# ifog-pcb-analogModule.net
KiCad netlist of a schematic drawn in Altium Designer
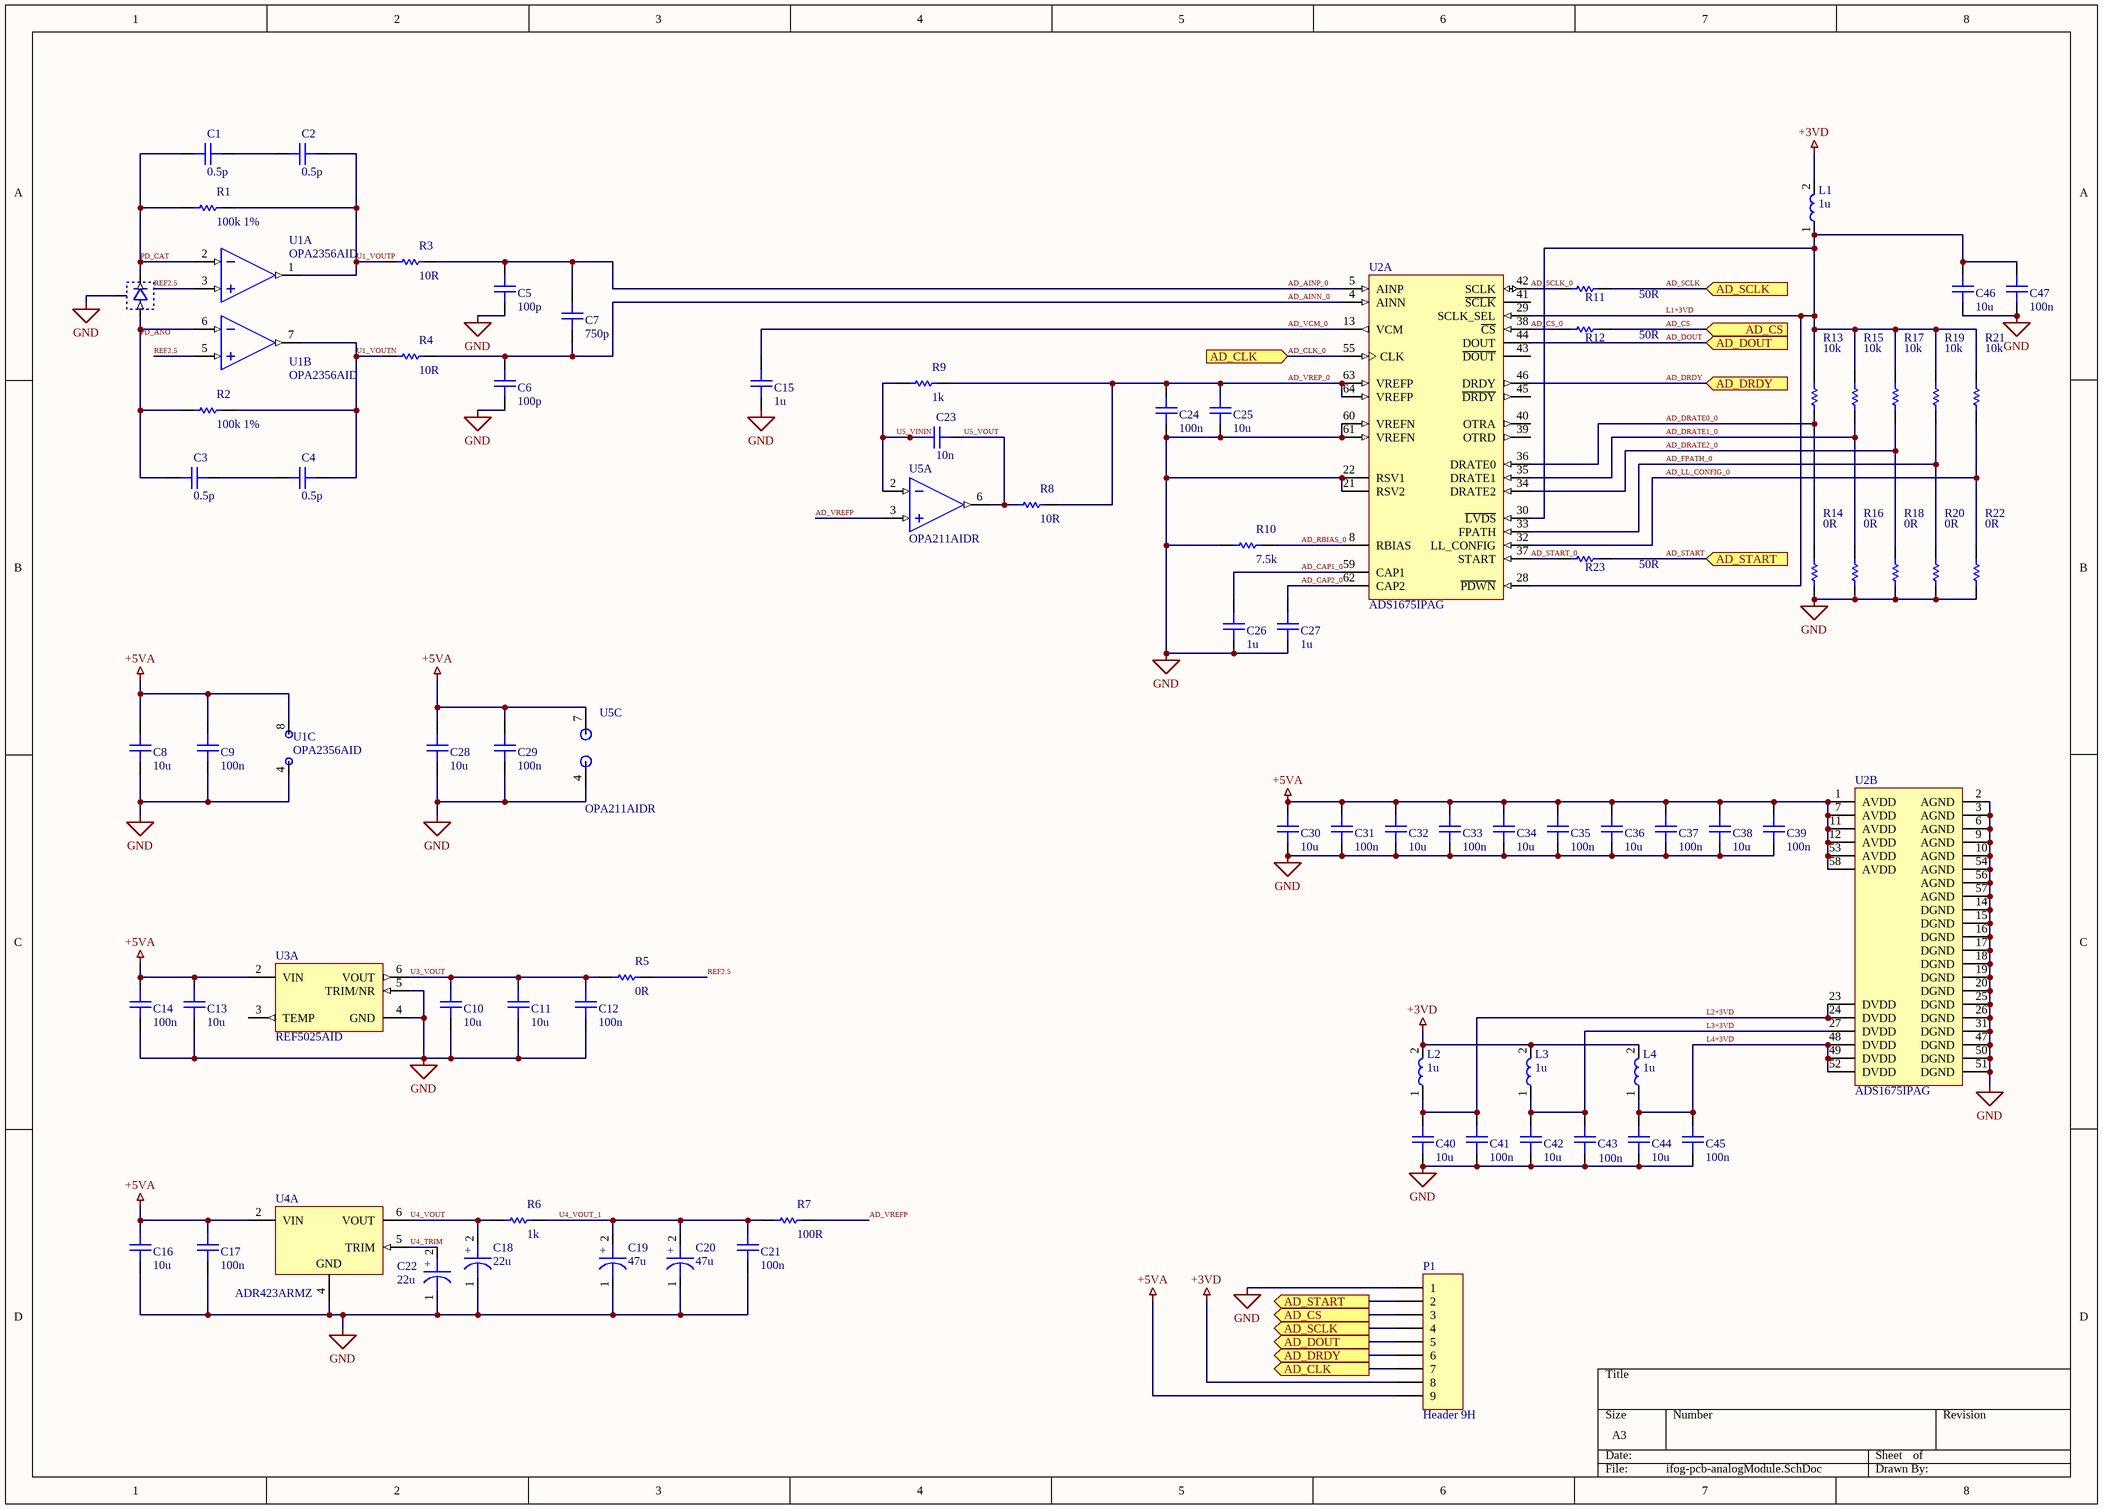
[diagram p0: ifog-pcb-analogModule.SchDoc]

(export (version "E")
  (design (tool "Eeschema 10.0.6"))
  (components
    (comp (ref "C1")
      (value "0.5p")
      (footprint "CAPACITOR_0603")
      (fields (field (name "PART NUMBER") "C0603C105K3RACTU") (field (name "MANUFACTURER") "KEMET"))
      (libsource (lib "ifog-pcb") (part "CAPACITOR_0603"))
    )
    (comp (ref "C2")
      (value "0.5p")
      (footprint "CAPACITOR_0603")
      (fields (field (name "PART NUMBER") "C0603C105K3RACTU") (field (name "MANUFACTURER") "KEMET"))
      (libsource (lib "ifog-pcb") (part "CAPACITOR_0603"))
    )
    (comp (ref "C3")
      (value "0.5p")
      (footprint "CAPACITOR_0603")
      (fields (field (name "PART NUMBER") "C0603C105K3RACTU") (field (name "MANUFACTURER") "KEMET"))
      (libsource (lib "ifog-pcb") (part "CAPACITOR_0603"))
    )
    (comp (ref "C4")
      (value "0.5p")
      (footprint "CAPACITOR_0603")
      (fields (field (name "PART NUMBER") "C0603C105K3RACTU") (field (name "MANUFACTURER") "KEMET"))
      (libsource (lib "ifog-pcb") (part "CAPACITOR_0603"))
    )
    (comp (ref "C5")
      (value "100p")
      (footprint "CAPACITOR_0603")
      (fields (field (name "PART NUMBER") "C0603C105K3RACTU") (field (name "MANUFACTURER") "KEMET"))
      (libsource (lib "ifog-pcb") (part "CAPACITOR_0603"))
    )
    (comp (ref "C6")
      (value "100p")
      (footprint "CAPACITOR_0603")
      (fields (field (name "PART NUMBER") "C0603C105K3RACTU") (field (name "MANUFACTURER") "KEMET"))
      (libsource (lib "ifog-pcb") (part "CAPACITOR_0603"))
    )
    (comp (ref "C7")
      (value "750p")
      (footprint "CAPACITOR_0603")
      (fields (field (name "PART NUMBER") "C0603C105K3RACTU") (field (name "MANUFACTURER") "KEMET"))
      (libsource (lib "ifog-pcb") (part "CAPACITOR_0603"))
    )
    (comp (ref "C8")
      (value "10u")
      (footprint "CAPACITOR_0603")
      (fields (field (name "PART NUMBER") "C0603C105K3RACTU") (field (name "MANUFACTURER") "KEMET"))
      (libsource (lib "ifog-pcb") (part "CAPACITOR_0603"))
    )
    (comp (ref "C9")
      (value "100n")
      (footprint "CAPACITOR_0603")
      (fields (field (name "PART NUMBER") "C0603C105K3RACTU") (field (name "MANUFACTURER") "KEMET"))
      (libsource (lib "ifog-pcb") (part "CAPACITOR_0603"))
    )
    (comp (ref "C10")
      (value "10u")
      (footprint "CAPACITOR_0603")
      (fields (field (name "PART NUMBER") "C0603C105K3RACTU") (field (name "MANUFACTURER") "KEMET"))
      (libsource (lib "ifog-pcb") (part "CAPACITOR_0603"))
    )
    (comp (ref "C11")
      (value "10u")
      (footprint "CAPACITOR_0603")
      (fields (field (name "PART NUMBER") "C0603C105K3RACTU") (field (name "MANUFACTURER") "KEMET"))
      (libsource (lib "ifog-pcb") (part "CAPACITOR_0603"))
    )
    (comp (ref "C12")
      (value "100n")
      (footprint "CAPACITOR_0603")
      (fields (field (name "PART NUMBER") "C0603C105K3RACTU") (field (name "MANUFACTURER") "KEMET"))
      (libsource (lib "ifog-pcb") (part "CAPACITOR_0603"))
    )
    (comp (ref "C13")
      (value "10u")
      (footprint "CAPACITOR_0603")
      (fields (field (name "PART NUMBER") "C0603C105K3RACTU") (field (name "MANUFACTURER") "KEMET"))
      (libsource (lib "ifog-pcb") (part "CAPACITOR_0603"))
    )
    (comp (ref "C14")
      (value "100n")
      (footprint "CAPACITOR_0603")
      (fields (field (name "PART NUMBER") "C0603C105K3RACTU") (field (name "MANUFACTURER") "KEMET"))
      (libsource (lib "ifog-pcb") (part "CAPACITOR_0603"))
    )
    (comp (ref "C15")
      (value "1u")
      (footprint "CAPACITOR_0603")
      (fields (field (name "PART NUMBER") "C0603C105K3RACTU") (field (name "MANUFACTURER") "KEMET"))
      (libsource (lib "ifog-pcb") (part "CAPACITOR_0603"))
    )
    (comp (ref "C16")
      (value "10u")
      (footprint "CAPACITOR_0603")
      (fields (field (name "PART NUMBER") "C0603C105K3RACTU") (field (name "MANUFACTURER") "KEMET"))
      (libsource (lib "ifog-pcb") (part "CAPACITOR_0603"))
    )
    (comp (ref "C17")
      (value "100n")
      (footprint "CAPACITOR_0603")
      (fields (field (name "PART NUMBER") "C0603C105K3RACTU") (field (name "MANUFACTURER") "KEMET"))
      (libsource (lib "ifog-pcb") (part "CAPACITOR_0603"))
    )
    (comp (ref "C18")
      (value "22u")
      (footprint "CAPACITOR_TANT_0603")
      (description "CAP TANT 0603")
      (fields (field (name "TOLERANCE") "20%") (field (name "MANUFACTURER") "Kyocera AVX"))
      (libsource (lib "ifog-pcb") (part "CAPACITOR_TANT_0603"))
    )
    (comp (ref "C19")
      (value "47u")
      (footprint "CAPACITOR_TANT_0603")
      (description "CAP TANT 0603")
      (fields (field (name "TOLERANCE") "20%") (field (name "MANUFACTURER") "Kyocera AVX"))
      (libsource (lib "ifog-pcb") (part "CAPACITOR_TANT_0603"))
    )
    (comp (ref "C20")
      (value "47u")
      (footprint "CAPACITOR_TANT_0603")
      (description "CAP TANT 0603")
      (fields (field (name "TOLERANCE") "20%") (field (name "MANUFACTURER") "Kyocera AVX"))
      (libsource (lib "ifog-pcb") (part "CAPACITOR_TANT_0603"))
    )
    (comp (ref "C21")
      (value "100n")
      (footprint "CAPACITOR_0603")
      (fields (field (name "PART NUMBER") "C0603C105K3RACTU") (field (name "MANUFACTURER") "KEMET"))
      (libsource (lib "ifog-pcb") (part "CAPACITOR_0603"))
    )
    (comp (ref "C22")
      (value "22u")
      (footprint "CAPACITOR_TANT_0603")
      (description "CAP TANT 0603")
      (fields (field (name "TOLERANCE") "20%") (field (name "MANUFACTURER") "Kyocera AVX"))
      (libsource (lib "ifog-pcb") (part "CAPACITOR_TANT_0603"))
    )
    (comp (ref "C23")
      (value "10n")
      (footprint "CAPACITOR_0603")
      (fields (field (name "PART NUMBER") "C0603C105K3RACTU") (field (name "MANUFACTURER") "KEMET"))
      (libsource (lib "ifog-pcb") (part "CAPACITOR_0603"))
    )
    (comp (ref "C24")
      (value "100n")
      (footprint "CAPACITOR_0603")
      (fields (field (name "PART NUMBER") "C0603C105K3RACTU") (field (name "MANUFACTURER") "KEMET"))
      (libsource (lib "ifog-pcb") (part "CAPACITOR_0603"))
    )
    (comp (ref "C25")
      (value "10u")
      (footprint "CAPACITOR_0603")
      (fields (field (name "PART NUMBER") "C0603C105K3RACTU") (field (name "MANUFACTURER") "KEMET"))
      (libsource (lib "ifog-pcb") (part "CAPACITOR_0603"))
    )
    (comp (ref "C26")
      (value "1u")
      (footprint "CAPACITOR_0603")
      (fields (field (name "PART NUMBER") "C0603C105K3RACTU") (field (name "MANUFACTURER") "KEMET"))
      (libsource (lib "ifog-pcb") (part "CAPACITOR_0603"))
    )
    (comp (ref "C27")
      (value "1u")
      (footprint "CAPACITOR_0603")
      (fields (field (name "PART NUMBER") "C0603C105K3RACTU") (field (name "MANUFACTURER") "KEMET"))
      (libsource (lib "ifog-pcb") (part "CAPACITOR_0603"))
    )
    (comp (ref "C28")
      (value "10u")
      (footprint "CAPACITOR_0603")
      (fields (field (name "PART NUMBER") "C0603C105K3RACTU") (field (name "MANUFACTURER") "KEMET"))
      (libsource (lib "ifog-pcb") (part "CAPACITOR_0603"))
    )
    (comp (ref "C29")
      (value "100n")
      (footprint "CAPACITOR_0603")
      (fields (field (name "PART NUMBER") "C0603C105K3RACTU") (field (name "MANUFACTURER") "KEMET"))
      (libsource (lib "ifog-pcb") (part "CAPACITOR_0603"))
    )
    (comp (ref "C30")
      (value "10u")
      (footprint "CAPACITOR_0603")
      (fields (field (name "PART NUMBER") "C0603C105K3RACTU") (field (name "MANUFACTURER") "KEMET"))
      (libsource (lib "ifog-pcb") (part "CAPACITOR_0603"))
    )
    (comp (ref "C31")
      (value "100n")
      (footprint "CAPACITOR_0603")
      (fields (field (name "PART NUMBER") "C0603C105K3RACTU") (field (name "MANUFACTURER") "KEMET"))
      (libsource (lib "ifog-pcb") (part "CAPACITOR_0603"))
    )
    (comp (ref "C32")
      (value "10u")
      (footprint "CAPACITOR_0603")
      (fields (field (name "PART NUMBER") "C0603C105K3RACTU") (field (name "MANUFACTURER") "KEMET"))
      (libsource (lib "ifog-pcb") (part "CAPACITOR_0603"))
    )
    (comp (ref "C33")
      (value "100n")
      (footprint "CAPACITOR_0603")
      (fields (field (name "PART NUMBER") "C0603C105K3RACTU") (field (name "MANUFACTURER") "KEMET"))
      (libsource (lib "ifog-pcb") (part "CAPACITOR_0603"))
    )
    (comp (ref "C34")
      (value "10u")
      (footprint "CAPACITOR_0603")
      (fields (field (name "PART NUMBER") "C0603C105K3RACTU") (field (name "MANUFACTURER") "KEMET"))
      (libsource (lib "ifog-pcb") (part "CAPACITOR_0603"))
    )
    (comp (ref "C35")
      (value "100n")
      (footprint "CAPACITOR_0603")
      (fields (field (name "PART NUMBER") "C0603C105K3RACTU") (field (name "MANUFACTURER") "KEMET"))
      (libsource (lib "ifog-pcb") (part "CAPACITOR_0603"))
    )
    (comp (ref "C36")
      (value "10u")
      (footprint "CAPACITOR_0603")
      (fields (field (name "PART NUMBER") "C0603C105K3RACTU") (field (name "MANUFACTURER") "KEMET"))
      (libsource (lib "ifog-pcb") (part "CAPACITOR_0603"))
    )
    (comp (ref "C37")
      (value "100n")
      (footprint "CAPACITOR_0603")
      (fields (field (name "PART NUMBER") "C0603C105K3RACTU") (field (name "MANUFACTURER") "KEMET"))
      (libsource (lib "ifog-pcb") (part "CAPACITOR_0603"))
    )
    (comp (ref "C38")
      (value "10u")
      (footprint "CAPACITOR_0603")
      (fields (field (name "PART NUMBER") "C0603C105K3RACTU") (field (name "MANUFACTURER") "KEMET"))
      (libsource (lib "ifog-pcb") (part "CAPACITOR_0603"))
    )
    (comp (ref "C39")
      (value "100n")
      (footprint "CAPACITOR_0603")
      (fields (field (name "PART NUMBER") "C0603C105K3RACTU") (field (name "MANUFACTURER") "KEMET"))
      (libsource (lib "ifog-pcb") (part "CAPACITOR_0603"))
    )
    (comp (ref "C40")
      (value "10u")
      (footprint "CAPACITOR_0603")
      (fields (field (name "PART NUMBER") "C0603C105K3RACTU") (field (name "MANUFACTURER") "KEMET"))
      (libsource (lib "ifog-pcb") (part "CAPACITOR_0603"))
    )
    (comp (ref "C41")
      (value "100n")
      (footprint "CAPACITOR_0603")
      (fields (field (name "PART NUMBER") "C0603C105K3RACTU") (field (name "MANUFACTURER") "KEMET"))
      (libsource (lib "ifog-pcb") (part "CAPACITOR_0603"))
    )
    (comp (ref "C42")
      (value "10u")
      (footprint "CAPACITOR_0603")
      (fields (field (name "PART NUMBER") "C0603C105K3RACTU") (field (name "MANUFACTURER") "KEMET"))
      (libsource (lib "ifog-pcb") (part "CAPACITOR_0603"))
    )
    (comp (ref "C43")
      (value "100n")
      (footprint "CAPACITOR_0603")
      (fields (field (name "PART NUMBER") "C0603C105K3RACTU") (field (name "MANUFACTURER") "KEMET"))
      (libsource (lib "ifog-pcb") (part "CAPACITOR_0603"))
    )
    (comp (ref "C44")
      (value "10u")
      (footprint "CAPACITOR_0603")
      (fields (field (name "PART NUMBER") "C0603C105K3RACTU") (field (name "MANUFACTURER") "KEMET"))
      (libsource (lib "ifog-pcb") (part "CAPACITOR_0603"))
    )
    (comp (ref "C45")
      (value "100n")
      (footprint "CAPACITOR_0603")
      (fields (field (name "PART NUMBER") "C0603C105K3RACTU") (field (name "MANUFACTURER") "KEMET"))
      (libsource (lib "ifog-pcb") (part "CAPACITOR_0603"))
    )
    (comp (ref "C46")
      (value "10u")
      (footprint "CAPACITOR_0603")
      (fields (field (name "PART NUMBER") "C0603C105K3RACTU") (field (name "MANUFACTURER") "KEMET"))
      (libsource (lib "ifog-pcb") (part "CAPACITOR_0603"))
    )
    (comp (ref "C47")
      (value "100n")
      (footprint "CAPACITOR_0603")
      (fields (field (name "PART NUMBER") "C0603C105K3RACTU") (field (name "MANUFACTURER") "KEMET"))
      (libsource (lib "ifog-pcb") (part "CAPACITOR_0603"))
    )
    (comp (ref "L1")
      (value "1u")
      (footprint "INDUCTOR_0603")
      (description "FIXED IND SMD")
      (fields (field (name "TOLERANCE") "20%") (field (name "MANUFACTURER") "Murata"))
      (libsource (lib "ifog-pcb") (part "INDUCTOR_0603"))
    )
    (comp (ref "L2")
      (value "1u")
      (footprint "INDUCTOR_0603")
      (description "FIXED IND SMD")
      (fields (field (name "TOLERANCE") "20%") (field (name "MANUFACTURER") "Murata"))
      (libsource (lib "ifog-pcb") (part "INDUCTOR_0603"))
    )
    (comp (ref "L3")
      (value "1u")
      (footprint "INDUCTOR_0603")
      (description "FIXED IND SMD")
      (fields (field (name "TOLERANCE") "20%") (field (name "MANUFACTURER") "Murata"))
      (libsource (lib "ifog-pcb") (part "INDUCTOR_0603"))
    )
    (comp (ref "L4")
      (value "1u")
      (footprint "INDUCTOR_0603")
      (description "FIXED IND SMD")
      (fields (field (name "TOLERANCE") "20%") (field (name "MANUFACTURER") "Murata"))
      (libsource (lib "ifog-pcb") (part "INDUCTOR_0603"))
    )
    (comp (ref "P1")
      (value "Header 9H")
      (footprint "HDR1X9H")
      (description "Header, 9-Pin, Right Angle")
      (fields (field (name "PUBLISHER") "Altium Limited"))
      (libsource (lib "Miscellaneous Connectors") (part "Header 9H"))
    )
    (comp (ref "PD1")
      (value "PDS123-CSA-C0102")
      (footprint "Photodetector")
      (description "Photodiode 3 pins")
      (libsource (lib "ifog-pcb") (part "PDS123-CSA-C0102"))
    )
    (comp (ref "R1")
      (value "100k 1%")
      (footprint "RESISTOR_0603")
      (description "Chip Resistor 0603 (1608 Metric), RoHS, Tape and Reel")
      (fields
        (field (name "MANUFACTURER") "Vishay")
        (field (name "MANUFACTURER PART NUMBER") "CRCW060310K0FKEA")
      )
      (libsource (lib "ifog-pcb") (part "RESISTOR_0603"))
    )
    (comp (ref "R2")
      (value "100k 1%")
      (footprint "RESISTOR_0603")
      (description "Chip Resistor 0603 (1608 Metric), RoHS, Tape and Reel")
      (fields
        (field (name "MANUFACTURER") "Vishay")
        (field (name "MANUFACTURER PART NUMBER") "CRCW060310K0FKEA")
      )
      (libsource (lib "ifog-pcb") (part "RESISTOR_0603"))
    )
    (comp (ref "R3")
      (value "10R")
      (footprint "RESISTOR_0603")
      (description "Chip Resistor 0603 (1608 Metric), RoHS, Tape and Reel")
      (fields
        (field (name "MANUFACTURER") "Vishay")
        (field (name "MANUFACTURER PART NUMBER") "CRCW060310K0FKEA")
      )
      (libsource (lib "ifog-pcb") (part "RESISTOR_0603"))
    )
    (comp (ref "R4")
      (value "10R")
      (footprint "RESISTOR_0603")
      (description "Chip Resistor 0603 (1608 Metric), RoHS, Tape and Reel")
      (fields
        (field (name "MANUFACTURER") "Vishay")
        (field (name "MANUFACTURER PART NUMBER") "CRCW060310K0FKEA")
      )
      (libsource (lib "ifog-pcb") (part "RESISTOR_0603"))
    )
    (comp (ref "R5")
      (value "0R")
      (footprint "RESISTOR_0603")
      (description "Chip Resistor 0603 (1608 Metric), RoHS, Tape and Reel")
      (fields
        (field (name "MANUFACTURER") "Vishay")
        (field (name "MANUFACTURER PART NUMBER") "CRCW060310K0FKEA")
      )
      (libsource (lib "ifog-pcb") (part "RESISTOR_0603"))
    )
    (comp (ref "R6")
      (value "1k")
      (footprint "RESISTOR_0603")
      (description "Chip Resistor 0603 (1608 Metric), RoHS, Tape and Reel")
      (fields
        (field (name "MANUFACTURER") "Vishay")
        (field (name "MANUFACTURER PART NUMBER") "CRCW060310K0FKEA")
      )
      (libsource (lib "ifog-pcb") (part "RESISTOR_0603"))
    )
    (comp (ref "R7")
      (value "100R")
      (footprint "RESISTOR_0603")
      (description "Chip Resistor 0603 (1608 Metric), RoHS, Tape and Reel")
      (fields
        (field (name "MANUFACTURER") "Vishay")
        (field (name "MANUFACTURER PART NUMBER") "CRCW060310K0FKEA")
      )
      (libsource (lib "ifog-pcb") (part "RESISTOR_0603"))
    )
    (comp (ref "R8")
      (value "10R")
      (footprint "RESISTOR_0603")
      (description "Chip Resistor 0603 (1608 Metric), RoHS, Tape and Reel")
      (fields
        (field (name "MANUFACTURER") "Vishay")
        (field (name "MANUFACTURER PART NUMBER") "CRCW060310K0FKEA")
      )
      (libsource (lib "ifog-pcb") (part "RESISTOR_0603"))
    )
    (comp (ref "R9")
      (value "1k")
      (footprint "RESISTOR_0603")
      (description "Chip Resistor 0603 (1608 Metric), RoHS, Tape and Reel")
      (fields
        (field (name "MANUFACTURER") "Vishay")
        (field (name "MANUFACTURER PART NUMBER") "CRCW060310K0FKEA")
      )
      (libsource (lib "ifog-pcb") (part "RESISTOR_0603"))
    )
    (comp (ref "R10")
      (value "7.5k")
      (footprint "RESISTOR_0603")
      (description "Chip Resistor 0603 (1608 Metric), RoHS, Tape and Reel")
      (fields
        (field (name "MANUFACTURER") "Vishay")
        (field (name "MANUFACTURER PART NUMBER") "CRCW060310K0FKEA")
      )
      (libsource (lib "ifog-pcb") (part "RESISTOR_0603"))
    )
    (comp (ref "R11")
      (value "50R")
      (footprint "RESISTOR_0603")
      (description "Chip Resistor 0603 (1608 Metric), RoHS, Tape and Reel")
      (fields
        (field (name "MANUFACTURER") "Vishay")
        (field (name "MANUFACTURER PART NUMBER") "CRCW060310K0FKEA")
      )
      (libsource (lib "ifog-pcb") (part "RESISTOR_0603"))
    )
    (comp (ref "R12")
      (value "50R")
      (footprint "RESISTOR_0603")
      (description "Chip Resistor 0603 (1608 Metric), RoHS, Tape and Reel")
      (fields
        (field (name "MANUFACTURER") "Vishay")
        (field (name "MANUFACTURER PART NUMBER") "CRCW060310K0FKEA")
      )
      (libsource (lib "ifog-pcb") (part "RESISTOR_0603"))
    )
    (comp (ref "R13")
      (value "10k")
      (footprint "RESISTOR_0603")
      (description "Chip Resistor 0603 (1608 Metric), RoHS, Tape and Reel")
      (fields
        (field (name "MANUFACTURER") "Vishay")
        (field (name "MANUFACTURER PART NUMBER") "CRCW060310K0FKEA")
      )
      (libsource (lib "ifog-pcb") (part "RESISTOR_0603"))
    )
    (comp (ref "R14")
      (value "0R")
      (footprint "RESISTOR_0603")
      (description "Chip Resistor 0603 (1608 Metric), RoHS, Tape and Reel")
      (fields
        (field (name "MANUFACTURER") "Vishay")
        (field (name "MANUFACTURER PART NUMBER") "CRCW060310K0FKEA")
      )
      (libsource (lib "ifog-pcb") (part "RESISTOR_0603"))
    )
    (comp (ref "R15")
      (value "10k")
      (footprint "RESISTOR_0603")
      (description "Chip Resistor 0603 (1608 Metric), RoHS, Tape and Reel")
      (fields
        (field (name "MANUFACTURER") "Vishay")
        (field (name "MANUFACTURER PART NUMBER") "CRCW060310K0FKEA")
      )
      (libsource (lib "ifog-pcb") (part "RESISTOR_0603"))
    )
    (comp (ref "R16")
      (value "0R")
      (footprint "RESISTOR_0603")
      (description "Chip Resistor 0603 (1608 Metric), RoHS, Tape and Reel")
      (fields
        (field (name "MANUFACTURER") "Vishay")
        (field (name "MANUFACTURER PART NUMBER") "CRCW060310K0FKEA")
      )
      (libsource (lib "ifog-pcb") (part "RESISTOR_0603"))
    )
    (comp (ref "R17")
      (value "10k")
      (footprint "RESISTOR_0603")
      (description "Chip Resistor 0603 (1608 Metric), RoHS, Tape and Reel")
      (fields
        (field (name "MANUFACTURER") "Vishay")
        (field (name "MANUFACTURER PART NUMBER") "CRCW060310K0FKEA")
      )
      (libsource (lib "ifog-pcb") (part "RESISTOR_0603"))
    )
    (comp (ref "R18")
      (value "0R")
      (footprint "RESISTOR_0603")
      (description "Chip Resistor 0603 (1608 Metric), RoHS, Tape and Reel")
      (fields
        (field (name "MANUFACTURER") "Vishay")
        (field (name "MANUFACTURER PART NUMBER") "CRCW060310K0FKEA")
      )
      (libsource (lib "ifog-pcb") (part "RESISTOR_0603"))
    )
    (comp (ref "R19")
      (value "10k")
      (footprint "RESISTOR_0603")
      (description "Chip Resistor 0603 (1608 Metric), RoHS, Tape and Reel")
      (fields
        (field (name "MANUFACTURER") "Vishay")
        (field (name "MANUFACTURER PART NUMBER") "CRCW060310K0FKEA")
      )
      (libsource (lib "ifog-pcb") (part "RESISTOR_0603"))
    )
    (comp (ref "R20")
      (value "0R")
      (footprint "RESISTOR_0603")
      (description "Chip Resistor 0603 (1608 Metric), RoHS, Tape and Reel")
      (fields
        (field (name "MANUFACTURER") "Vishay")
        (field (name "MANUFACTURER PART NUMBER") "CRCW060310K0FKEA")
      )
      (libsource (lib "ifog-pcb") (part "RESISTOR_0603"))
    )
    (comp (ref "R21")
      (value "10k")
      (footprint "RESISTOR_0603")
      (description "Chip Resistor 0603 (1608 Metric), RoHS, Tape and Reel")
      (fields
        (field (name "MANUFACTURER") "Vishay")
        (field (name "MANUFACTURER PART NUMBER") "CRCW060310K0FKEA")
      )
      (libsource (lib "ifog-pcb") (part "RESISTOR_0603"))
    )
    (comp (ref "R22")
      (value "0R")
      (footprint "RESISTOR_0603")
      (description "Chip Resistor 0603 (1608 Metric), RoHS, Tape and Reel")
      (fields
        (field (name "MANUFACTURER") "Vishay")
        (field (name "MANUFACTURER PART NUMBER") "CRCW060310K0FKEA")
      )
      (libsource (lib "ifog-pcb") (part "RESISTOR_0603"))
    )
    (comp (ref "R23")
      (value "50R")
      (footprint "RESISTOR_0603")
      (description "Chip Resistor 0603 (1608 Metric), RoHS, Tape and Reel")
      (fields
        (field (name "MANUFACTURER") "Vishay")
        (field (name "MANUFACTURER PART NUMBER") "CRCW060310K0FKEA")
      )
      (libsource (lib "ifog-pcb") (part "RESISTOR_0603"))
    )
    (comp (ref "U1")
      (value "OPA2356AID")
      (footprint "OPA2356_SOIC8")
      (fields (field (name "MANUFACTURER") "Texas Instruments"))
      (libsource (lib "ifog-pcb") (part "OPA2356AID"))
    )
    (comp (ref "U2")
      (value "ADS1675IPAG")
      (footprint "TI-PAG64_L")
      (description "4 MSPS, 24-Bit ADC, -40 to 85 degC, 64-pin QFP (PAG64), Green (RoHS & no Sb/Br)")
      (fields (field (name "MANUFACTURER") "Texas Instruments"))
      (libsource (lib "ifog-pcb") (part "ADS1675"))
    )
    (comp (ref "U3")
      (value "REF5025AID")
      (footprint "OPA2356_SOIC8")
      (fields (field (name "MANUFACTURER") "Texas Instruments"))
      (libsource (lib "ifog-pcb") (part "REF5025AID"))
    )
    (comp (ref "U4")
      (value "ADR423ARMZ")
      (footprint "ADR423_SOP8")
      (fields (field (name "MANUFACTURER") "Analog Devices"))
      (libsource (lib "ifog-pcb") (part "ADR423ARMZ"))
    )
    (comp (ref "U5")
      (value "OPA211AIDR")
      (footprint "OPA211_SOIC8")
      (fields (field (name "MANUFACTURER") "Texas Instruments"))
      (libsource (lib "ifog-pcb") (part "OPA211AIDR"))
    )
  )
  (nets
    (net (code "1") (name "+3VD") (class "Default")
      (node (ref "L1") (pin "2") (pinfunction "2_2") (pintype "passive"))
      (node (ref "L2") (pin "2") (pinfunction "2_2") (pintype "passive"))
      (node (ref "L3") (pin "2") (pinfunction "2_2") (pintype "passive"))
      (node (ref "L4") (pin "2") (pinfunction "2_2") (pintype "passive"))
      (node (ref "P1") (pin "8") (pinfunction "8_8") (pintype "passive"))
    )
    (net (code "2") (name "+5VA") (class "Default")
      (node (ref "C13") (pin "2") (pinfunction "2_2") (pintype "passive"))
      (node (ref "C14") (pin "2") (pinfunction "2_2") (pintype "passive"))
      (node (ref "C16") (pin "2") (pinfunction "2_2") (pintype "passive"))
      (node (ref "C17") (pin "2") (pinfunction "2_2") (pintype "passive"))
      (node (ref "C28") (pin "2") (pinfunction "2_2") (pintype "passive"))
      (node (ref "C29") (pin "2") (pinfunction "2_2") (pintype "passive"))
      (node (ref "C30") (pin "2") (pinfunction "2_2") (pintype "passive"))
      (node (ref "C31") (pin "2") (pinfunction "2_2") (pintype "passive"))
      (node (ref "C32") (pin "2") (pinfunction "2_2") (pintype "passive"))
      (node (ref "C33") (pin "2") (pinfunction "2_2") (pintype "passive"))
      (node (ref "C34") (pin "2") (pinfunction "2_2") (pintype "passive"))
      (node (ref "C35") (pin "2") (pinfunction "2_2") (pintype "passive"))
      (node (ref "C36") (pin "2") (pinfunction "2_2") (pintype "passive"))
      (node (ref "C37") (pin "2") (pinfunction "2_2") (pintype "passive"))
      (node (ref "C38") (pin "2") (pinfunction "2_2") (pintype "passive"))
      (node (ref "C39") (pin "2") (pinfunction "2_2") (pintype "passive"))
      (node (ref "C8") (pin "2") (pinfunction "2_2") (pintype "passive"))
      (node (ref "C9") (pin "2") (pinfunction "2_2") (pintype "passive"))
      (node (ref "P1") (pin "9") (pinfunction "9_9") (pintype "passive"))
      (node (ref "U1") (pin "8") (pinfunction "V+_8") (pintype "power_in"))
      (node (ref "U2") (pin "1") (pinfunction "AVDD_1") (pintype "power_in"))
      (node (ref "U2") (pin "11") (pinfunction "AVDD_11") (pintype "power_in"))
      (node (ref "U2") (pin "12") (pinfunction "AVDD_12") (pintype "power_in"))
      (node (ref "U2") (pin "53") (pinfunction "AVDD_53") (pintype "power_in"))
      (node (ref "U2") (pin "58") (pinfunction "AVDD_58") (pintype "power_in"))
      (node (ref "U2") (pin "7") (pinfunction "AVDD_7") (pintype "power_in"))
      (node (ref "U3") (pin "2") (pinfunction "VIN_2") (pintype "power_in"))
      (node (ref "U4") (pin "2") (pinfunction "VIN_2") (pintype "power_in"))
      (node (ref "U5") (pin "7") (pinfunction "V+_7") (pintype "power_in"))
    )
    (net (code "3") (name "/AD_AINN_0") (class "Default")
      (node (ref "C6") (pin "2") (pinfunction "2_2") (pintype "passive"))
      (node (ref "C7") (pin "1") (pinfunction "1_1") (pintype "passive"))
      (node (ref "R4") (pin "2") (pinfunction "2_2") (pintype "passive"))
      (node (ref "U2") (pin "4") (pinfunction "AINN_4") (pintype "input"))
    )
    (net (code "4") (name "/AD_AINP_0") (class "Default")
      (node (ref "C5") (pin "2") (pinfunction "2_2") (pintype "passive"))
      (node (ref "C7") (pin "2") (pinfunction "2_2") (pintype "passive"))
      (node (ref "R3") (pin "2") (pinfunction "2_2") (pintype "passive"))
      (node (ref "U2") (pin "5") (pinfunction "AINP_5") (pintype "input"))
    )
    (net (code "5") (name "/AD_CAP1_0") (class "Default")
      (node (ref "C26") (pin "2") (pinfunction "2_2") (pintype "passive"))
      (node (ref "U2") (pin "59") (pinfunction "CAP1_59") (pintype "passive"))
    )
    (net (code "6") (name "/AD_CAP2_0") (class "Default")
      (node (ref "C27") (pin "2") (pinfunction "2_2") (pintype "passive"))
      (node (ref "U2") (pin "62") (pinfunction "CAP2_62") (pintype "passive"))
    )
    (net (code "7") (name "/AD_CLK_0") (class "Default")
      (node (ref "P1") (pin "7") (pinfunction "7_7") (pintype "passive"))
      (node (ref "U2") (pin "55") (pinfunction "CLK_55") (pintype "input"))
    )
    (net (code "8") (name "/AD_CS") (class "Default")
      (node (ref "P1") (pin "3") (pinfunction "3_3") (pintype "passive"))
      (node (ref "R12") (pin "2") (pinfunction "2_2") (pintype "passive"))
    )
    (net (code "9") (name "/AD_CS_0") (class "Default")
      (node (ref "R12") (pin "1") (pinfunction "1_1") (pintype "passive"))
      (node (ref "U2") (pin "38") (pinfunction "~{CS}_38") (pintype "input"))
    )
    (net (code "10") (name "/AD_DOUT") (class "Default")
      (node (ref "P1") (pin "5") (pinfunction "5_5") (pintype "passive"))
      (node (ref "U2") (pin "44") (pinfunction "DOUT_44") (pintype "tri_state"))
    )
    (net (code "11") (name "/AD_DRATE0_0") (class "Default")
      (node (ref "R13") (pin "1") (pinfunction "1_1") (pintype "passive"))
      (node (ref "R14") (pin "2") (pinfunction "2_2") (pintype "passive"))
      (node (ref "U2") (pin "36") (pinfunction "DRATE0_36") (pintype "input"))
    )
    (net (code "12") (name "/AD_DRATE1_0") (class "Default")
      (node (ref "R15") (pin "1") (pinfunction "1_1") (pintype "passive"))
      (node (ref "R16") (pin "2") (pinfunction "2_2") (pintype "passive"))
      (node (ref "U2") (pin "35") (pinfunction "DRATE1_35") (pintype "input"))
    )
    (net (code "13") (name "/AD_DRATE2_0") (class "Default")
      (node (ref "R17") (pin "1") (pinfunction "1_1") (pintype "passive"))
      (node (ref "R18") (pin "2") (pinfunction "2_2") (pintype "passive"))
      (node (ref "U2") (pin "34") (pinfunction "DRATE2_34") (pintype "input"))
    )
    (net (code "14") (name "/AD_DRDY") (class "Default")
      (node (ref "P1") (pin "6") (pinfunction "6_6") (pintype "passive"))
      (node (ref "U2") (pin "46") (pinfunction "DRDY_46") (pintype "output"))
    )
    (net (code "15") (name "/AD_FPATH_0") (class "Default")
      (node (ref "R19") (pin "1") (pinfunction "1_1") (pintype "passive"))
      (node (ref "R20") (pin "2") (pinfunction "2_2") (pintype "passive"))
      (node (ref "U2") (pin "33") (pinfunction "FPATH_33") (pintype "input"))
    )
    (net (code "16") (name "/AD_LL_CONFIG_0") (class "Default")
      (node (ref "R21") (pin "1") (pinfunction "1_1") (pintype "passive"))
      (node (ref "R22") (pin "2") (pinfunction "2_2") (pintype "passive"))
      (node (ref "U2") (pin "32") (pinfunction "LL_CONFIG_32") (pintype "input"))
    )
    (net (code "17") (name "/AD_RBIAS_0") (class "Default")
      (node (ref "R10") (pin "2") (pinfunction "2_2") (pintype "passive"))
      (node (ref "U2") (pin "8") (pinfunction "RBIAS_8") (pintype "passive"))
    )
    (net (code "18") (name "/AD_SCLK") (class "Default")
      (node (ref "P1") (pin "4") (pinfunction "4_4") (pintype "passive"))
      (node (ref "R11") (pin "2") (pinfunction "2_2") (pintype "passive"))
    )
    (net (code "19") (name "/AD_SCLK_0") (class "Default")
      (node (ref "R11") (pin "1") (pinfunction "1_1") (pintype "passive"))
      (node (ref "U2") (pin "42") (pinfunction "SCLK_42") (pintype "bidirectional"))
    )
    (net (code "20") (name "/AD_START") (class "Default")
      (node (ref "P1") (pin "2") (pinfunction "2_2") (pintype "passive"))
      (node (ref "R23") (pin "2") (pinfunction "2_2") (pintype "passive"))
    )
    (net (code "21") (name "/AD_START_0") (class "Default")
      (node (ref "R23") (pin "1") (pinfunction "1_1") (pintype "passive"))
      (node (ref "U2") (pin "37") (pinfunction "START_37") (pintype "input"))
    )
    (net (code "22") (name "/AD_VCM_0") (class "Default")
      (node (ref "C15") (pin "2") (pinfunction "2_2") (pintype "passive"))
      (node (ref "U2") (pin "13") (pinfunction "VCM_13") (pintype "output"))
    )
    (net (code "23") (name "/AD_VREFP") (class "Default")
      (node (ref "R7") (pin "2") (pinfunction "2_2") (pintype "passive"))
      (node (ref "U5") (pin "3") (pinfunction "IN+_3") (pintype "input"))
    )
    (net (code "24") (name "/AD_VREP_0") (class "Default")
      (node (ref "C24") (pin "2") (pinfunction "2_2") (pintype "passive"))
      (node (ref "C25") (pin "2") (pinfunction "2_2") (pintype "passive"))
      (node (ref "R8") (pin "2") (pinfunction "2_2") (pintype "passive"))
      (node (ref "R9") (pin "2") (pinfunction "2_2") (pintype "passive"))
      (node (ref "U2") (pin "63") (pinfunction "VREFP_63") (pintype "input"))
      (node (ref "U2") (pin "64") (pinfunction "VREFP_64") (pintype "input"))
    )
    (net (code "25") (name "/L1+3VD") (class "Default")
      (node (ref "C46") (pin "2") (pinfunction "2_2") (pintype "passive"))
      (node (ref "C47") (pin "2") (pinfunction "2_2") (pintype "passive"))
      (node (ref "L1") (pin "1") (pinfunction "1_1") (pintype "passive"))
      (node (ref "R13") (pin "2") (pinfunction "2_2") (pintype "passive"))
      (node (ref "R15") (pin "2") (pinfunction "2_2") (pintype "passive"))
      (node (ref "R17") (pin "2") (pinfunction "2_2") (pintype "passive"))
      (node (ref "R19") (pin "2") (pinfunction "2_2") (pintype "passive"))
      (node (ref "R21") (pin "2") (pinfunction "2_2") (pintype "passive"))
      (node (ref "U2") (pin "28") (pinfunction "~{PDWN}_28") (pintype "input"))
      (node (ref "U2") (pin "29") (pinfunction "SCLK_SEL_29") (pintype "input"))
      (node (ref "U2") (pin "30") (pinfunction "~{LVDS}_30") (pintype "input"))
    )
    (net (code "26") (name "/L2+3VD") (class "Default")
      (node (ref "C40") (pin "2") (pinfunction "2_2") (pintype "passive"))
      (node (ref "C41") (pin "2") (pinfunction "2_2") (pintype "passive"))
      (node (ref "L2") (pin "1") (pinfunction "1_1") (pintype "passive"))
      (node (ref "U2") (pin "23") (pinfunction "DVDD_23") (pintype "power_in"))
      (node (ref "U2") (pin "24") (pinfunction "DVDD_24") (pintype "power_in"))
    )
    (net (code "27") (name "/L3+3VD") (class "Default")
      (node (ref "C42") (pin "2") (pinfunction "2_2") (pintype "passive"))
      (node (ref "C43") (pin "2") (pinfunction "2_2") (pintype "passive"))
      (node (ref "L3") (pin "1") (pinfunction "1_1") (pintype "passive"))
      (node (ref "U2") (pin "27") (pinfunction "DVDD_27") (pintype "power_in"))
    )
    (net (code "28") (name "/L4+3VD") (class "Default")
      (node (ref "C44") (pin "2") (pinfunction "2_2") (pintype "passive"))
      (node (ref "C45") (pin "2") (pinfunction "2_2") (pintype "passive"))
      (node (ref "L4") (pin "1") (pinfunction "1_1") (pintype "passive"))
      (node (ref "U2") (pin "48") (pinfunction "DVDD_48") (pintype "power_in"))
      (node (ref "U2") (pin "49") (pinfunction "DVDD_49") (pintype "power_in"))
      (node (ref "U2") (pin "52") (pinfunction "DVDD_52") (pintype "power_in"))
    )
    (net (code "29") (name "/PD_ANO") (class "Default")
      (node (ref "C3") (pin "2") (pinfunction "2_2") (pintype "passive"))
      (node (ref "PD1") (pin "P") (pinfunction "P_P") (pintype "input"))
      (node (ref "R2") (pin "1") (pinfunction "1_1") (pintype "passive"))
      (node (ref "U1") (pin "6") (pinfunction "IN_B-_6") (pintype "input"))
    )
    (net (code "30") (name "/PD_CAT") (class "Default")
      (node (ref "C1") (pin "2") (pinfunction "2_2") (pintype "passive"))
      (node (ref "PD1") (pin "N") (pinfunction "N_N") (pintype "output"))
      (node (ref "R1") (pin "1") (pinfunction "1_1") (pintype "passive"))
      (node (ref "U1") (pin "2") (pinfunction "IN_A-_2") (pintype "input"))
    )
    (net (code "31") (name "/REF2.5") (class "Default")
      (node (ref "R5") (pin "2") (pinfunction "2_2") (pintype "passive"))
      (node (ref "U1") (pin "3") (pinfunction "IN_A+_3") (pintype "input"))
      (node (ref "U1") (pin "5") (pinfunction "IN_B+_5") (pintype "input"))
    )
    (net (code "32") (name "/U1_VOUTN") (class "Default")
      (node (ref "C4") (pin "1") (pinfunction "1_1") (pintype "passive"))
      (node (ref "R2") (pin "2") (pinfunction "2_2") (pintype "passive"))
      (node (ref "R4") (pin "1") (pinfunction "1_1") (pintype "passive"))
      (node (ref "U1") (pin "7") (pinfunction "OUT_B_7") (pintype "output"))
    )
    (net (code "33") (name "/U1_VOUTP") (class "Default")
      (node (ref "C2") (pin "1") (pinfunction "1_1") (pintype "passive"))
      (node (ref "R1") (pin "2") (pinfunction "2_2") (pintype "passive"))
      (node (ref "R3") (pin "1") (pinfunction "1_1") (pintype "passive"))
      (node (ref "U1") (pin "1") (pinfunction "OUT_A_1") (pintype "output"))
    )
    (net (code "34") (name "/U3_VOUT") (class "Default")
      (node (ref "C10") (pin "2") (pinfunction "2_2") (pintype "passive"))
      (node (ref "C11") (pin "2") (pinfunction "2_2") (pintype "passive"))
      (node (ref "C12") (pin "2") (pinfunction "2_2") (pintype "passive"))
      (node (ref "R5") (pin "1") (pinfunction "1_1") (pintype "passive"))
      (node (ref "U3") (pin "6") (pinfunction "VOUT_6") (pintype "output"))
    )
    (net (code "35") (name "/U4_TRIM") (class "Default")
      (node (ref "C22") (pin "2") (pinfunction "A_2") (pintype "passive"))
      (node (ref "U4") (pin "5") (pinfunction "TRIM_5") (pintype "input"))
    )
    (net (code "36") (name "/U4_VOUT") (class "Default")
      (node (ref "C18") (pin "2") (pinfunction "A_2") (pintype "passive"))
      (node (ref "R6") (pin "1") (pinfunction "1_1") (pintype "passive"))
      (node (ref "U4") (pin "6") (pinfunction "VOUT_6") (pintype "power_in"))
    )
    (net (code "37") (name "/U4_VOUT_1") (class "Default")
      (node (ref "C19") (pin "2") (pinfunction "A_2") (pintype "passive"))
      (node (ref "C20") (pin "2") (pinfunction "A_2") (pintype "passive"))
      (node (ref "C21") (pin "2") (pinfunction "2_2") (pintype "passive"))
      (node (ref "R6") (pin "2") (pinfunction "2_2") (pintype "passive"))
      (node (ref "R7") (pin "1") (pinfunction "1_1") (pintype "passive"))
    )
    (net (code "38") (name "/U5_VININ") (class "Default")
      (node (ref "C23") (pin "2") (pinfunction "2_2") (pintype "passive"))
      (node (ref "R9") (pin "1") (pinfunction "1_1") (pintype "passive"))
      (node (ref "U5") (pin "2") (pinfunction "IN-_2") (pintype "input"))
    )
    (net (code "39") (name "/U5_VOUT") (class "Default")
      (node (ref "C23") (pin "1") (pinfunction "1_1") (pintype "passive"))
      (node (ref "R8") (pin "1") (pinfunction "1_1") (pintype "passive"))
      (node (ref "U5") (pin "6") (pinfunction "OUT_6") (pintype "output"))
    )
    (net (code "40") (name "GND") (class "Default")
      (node (ref "C10") (pin "1") (pinfunction "1_1") (pintype "passive"))
      (node (ref "C11") (pin "1") (pinfunction "1_1") (pintype "passive"))
      (node (ref "C12") (pin "1") (pinfunction "1_1") (pintype "passive"))
      (node (ref "C13") (pin "1") (pinfunction "1_1") (pintype "passive"))
      (node (ref "C14") (pin "1") (pinfunction "1_1") (pintype "passive"))
      (node (ref "C15") (pin "1") (pinfunction "1_1") (pintype "passive"))
      (node (ref "C16") (pin "1") (pinfunction "1_1") (pintype "passive"))
      (node (ref "C17") (pin "1") (pinfunction "1_1") (pintype "passive"))
      (node (ref "C18") (pin "1") (pinfunction "C_1") (pintype "passive"))
      (node (ref "C19") (pin "1") (pinfunction "C_1") (pintype "passive"))
      (node (ref "C20") (pin "1") (pinfunction "C_1") (pintype "passive"))
      (node (ref "C21") (pin "1") (pinfunction "1_1") (pintype "passive"))
      (node (ref "C22") (pin "1") (pinfunction "C_1") (pintype "passive"))
      (node (ref "C24") (pin "1") (pinfunction "1_1") (pintype "passive"))
      (node (ref "C25") (pin "1") (pinfunction "1_1") (pintype "passive"))
      (node (ref "C26") (pin "1") (pinfunction "1_1") (pintype "passive"))
      (node (ref "C27") (pin "1") (pinfunction "1_1") (pintype "passive"))
      (node (ref "C28") (pin "1") (pinfunction "1_1") (pintype "passive"))
      (node (ref "C29") (pin "1") (pinfunction "1_1") (pintype "passive"))
      (node (ref "C30") (pin "1") (pinfunction "1_1") (pintype "passive"))
      (node (ref "C31") (pin "1") (pinfunction "1_1") (pintype "passive"))
      (node (ref "C32") (pin "1") (pinfunction "1_1") (pintype "passive"))
      (node (ref "C33") (pin "1") (pinfunction "1_1") (pintype "passive"))
      (node (ref "C34") (pin "1") (pinfunction "1_1") (pintype "passive"))
      (node (ref "C35") (pin "1") (pinfunction "1_1") (pintype "passive"))
      (node (ref "C36") (pin "1") (pinfunction "1_1") (pintype "passive"))
      (node (ref "C37") (pin "1") (pinfunction "1_1") (pintype "passive"))
      (node (ref "C38") (pin "1") (pinfunction "1_1") (pintype "passive"))
      (node (ref "C39") (pin "1") (pinfunction "1_1") (pintype "passive"))
      (node (ref "C40") (pin "1") (pinfunction "1_1") (pintype "passive"))
      (node (ref "C41") (pin "1") (pinfunction "1_1") (pintype "passive"))
      (node (ref "C42") (pin "1") (pinfunction "1_1") (pintype "passive"))
      (node (ref "C43") (pin "1") (pinfunction "1_1") (pintype "passive"))
      (node (ref "C44") (pin "1") (pinfunction "1_1") (pintype "passive"))
      (node (ref "C45") (pin "1") (pinfunction "1_1") (pintype "passive"))
      (node (ref "C46") (pin "1") (pinfunction "1_1") (pintype "passive"))
      (node (ref "C47") (pin "1") (pinfunction "1_1") (pintype "passive"))
      (node (ref "C5") (pin "1") (pinfunction "1_1") (pintype "passive"))
      (node (ref "C6") (pin "1") (pinfunction "1_1") (pintype "passive"))
      (node (ref "C8") (pin "1") (pinfunction "1_1") (pintype "passive"))
      (node (ref "C9") (pin "1") (pinfunction "1_1") (pintype "passive"))
      (node (ref "P1") (pin "1") (pinfunction "1_1") (pintype "passive"))
      (node (ref "PD1") (pin "GND") (pinfunction "GND_GND") (pintype "passive"))
      (node (ref "R10") (pin "1") (pinfunction "1_1") (pintype "passive"))
      (node (ref "R14") (pin "1") (pinfunction "1_1") (pintype "passive"))
      (node (ref "R16") (pin "1") (pinfunction "1_1") (pintype "passive"))
      (node (ref "R18") (pin "1") (pinfunction "1_1") (pintype "passive"))
      (node (ref "R20") (pin "1") (pinfunction "1_1") (pintype "passive"))
      (node (ref "R22") (pin "1") (pinfunction "1_1") (pintype "passive"))
      (node (ref "U1") (pin "4") (pinfunction "V-_4") (pintype "power_in"))
      (node (ref "U2") (pin "10") (pinfunction "AGND_10") (pintype "power_in"))
      (node (ref "U2") (pin "14") (pinfunction "DGND_14") (pintype "power_in"))
      (node (ref "U2") (pin "15") (pinfunction "DGND_15") (pintype "power_in"))
      (node (ref "U2") (pin "16") (pinfunction "DGND_16") (pintype "power_in"))
      (node (ref "U2") (pin "17") (pinfunction "DGND_17") (pintype "power_in"))
      (node (ref "U2") (pin "18") (pinfunction "DGND_18") (pintype "power_in"))
      (node (ref "U2") (pin "19") (pinfunction "DGND_19") (pintype "power_in"))
      (node (ref "U2") (pin "2") (pinfunction "AGND_2") (pintype "power_in"))
      (node (ref "U2") (pin "20") (pinfunction "DGND_20") (pintype "power_in"))
      (node (ref "U2") (pin "21") (pinfunction "RSV2_21") (pintype "passive"))
      (node (ref "U2") (pin "22") (pinfunction "RSV1_22") (pintype "passive"))
      (node (ref "U2") (pin "25") (pinfunction "DGND_25") (pintype "power_in"))
      (node (ref "U2") (pin "26") (pinfunction "DGND_26") (pintype "power_in"))
      (node (ref "U2") (pin "3") (pinfunction "AGND_3") (pintype "power_in"))
      (node (ref "U2") (pin "31") (pinfunction "DGND_31") (pintype "power_in"))
      (node (ref "U2") (pin "47") (pinfunction "DGND_47") (pintype "power_in"))
      (node (ref "U2") (pin "50") (pinfunction "DGND_50") (pintype "power_in"))
      (node (ref "U2") (pin "51") (pinfunction "DGND_51") (pintype "power_in"))
      (node (ref "U2") (pin "54") (pinfunction "AGND_54") (pintype "power_in"))
      (node (ref "U2") (pin "56") (pinfunction "AGND_56") (pintype "power_in"))
      (node (ref "U2") (pin "57") (pinfunction "AGND_57") (pintype "power_in"))
      (node (ref "U2") (pin "6") (pinfunction "AGND_6") (pintype "power_in"))
      (node (ref "U2") (pin "60") (pinfunction "VREFN_60") (pintype "input"))
      (node (ref "U2") (pin "61") (pinfunction "VREFN_61") (pintype "input"))
      (node (ref "U2") (pin "9") (pinfunction "AGND_9") (pintype "power_in"))
      (node (ref "U3") (pin "4") (pinfunction "GND_4") (pintype "power_in"))
      (node (ref "U3") (pin "5") (pinfunction "TRIM/NR_5") (pintype "input"))
      (node (ref "U4") (pin "4") (pinfunction "GND_4") (pintype "power_in"))
      (node (ref "U5") (pin "4") (pinfunction "V-_4") (pintype "power_in"))
    )
    (net (code "41") (name "Net-(C1-Pad1)") (class "Default")
      (node (ref "C1") (pin "1") (pinfunction "1_1") (pintype "passive"))
      (node (ref "C2") (pin "2") (pinfunction "2_2") (pintype "passive"))
    )
    (net (code "42") (name "Net-(C3-Pad1)") (class "Default")
      (node (ref "C3") (pin "1") (pinfunction "1_1") (pintype "passive"))
      (node (ref "C4") (pin "2") (pinfunction "2_2") (pintype "passive"))
    )
    (net (code "43") (name "unconnected-(U2A-OTRA-Pad40)") (class "Default")
      (node (ref "U2") (pin "40") (pinfunction "OTRA_40") (pintype "output"))
    )
    (net (code "44") (name "unconnected-(U2A-OTRD-Pad39)") (class "Default")
      (node (ref "U2") (pin "39") (pinfunction "OTRD_39") (pintype "output"))
    )
    (net (code "45") (name "unconnected-(U2A-~{DOUT}-Pad43)") (class "Default")
      (node (ref "U2") (pin "43") (pinfunction "~{DOUT}_43") (pintype "tri_state"))
    )
    (net (code "46") (name "unconnected-(U2A-~{DRDY}-Pad45)") (class "Default")
      (node (ref "U2") (pin "45") (pinfunction "~{DRDY}_45") (pintype "output"))
    )
    (net (code "47") (name "unconnected-(U2A-~{SCLK}-Pad41)") (class "Default")
      (node (ref "U2") (pin "41") (pinfunction "~{SCLK}_41") (pintype "tri_state"))
    )
    (net (code "48") (name "unconnected-(U3A-TEMP-Pad3)") (class "Default")
      (node (ref "U3") (pin "3") (pinfunction "TEMP_3") (pintype "output"))
    )
  )
)
